# AD9102_DDS.net
KiCad netlist of a schematic drawn in Altium Designer
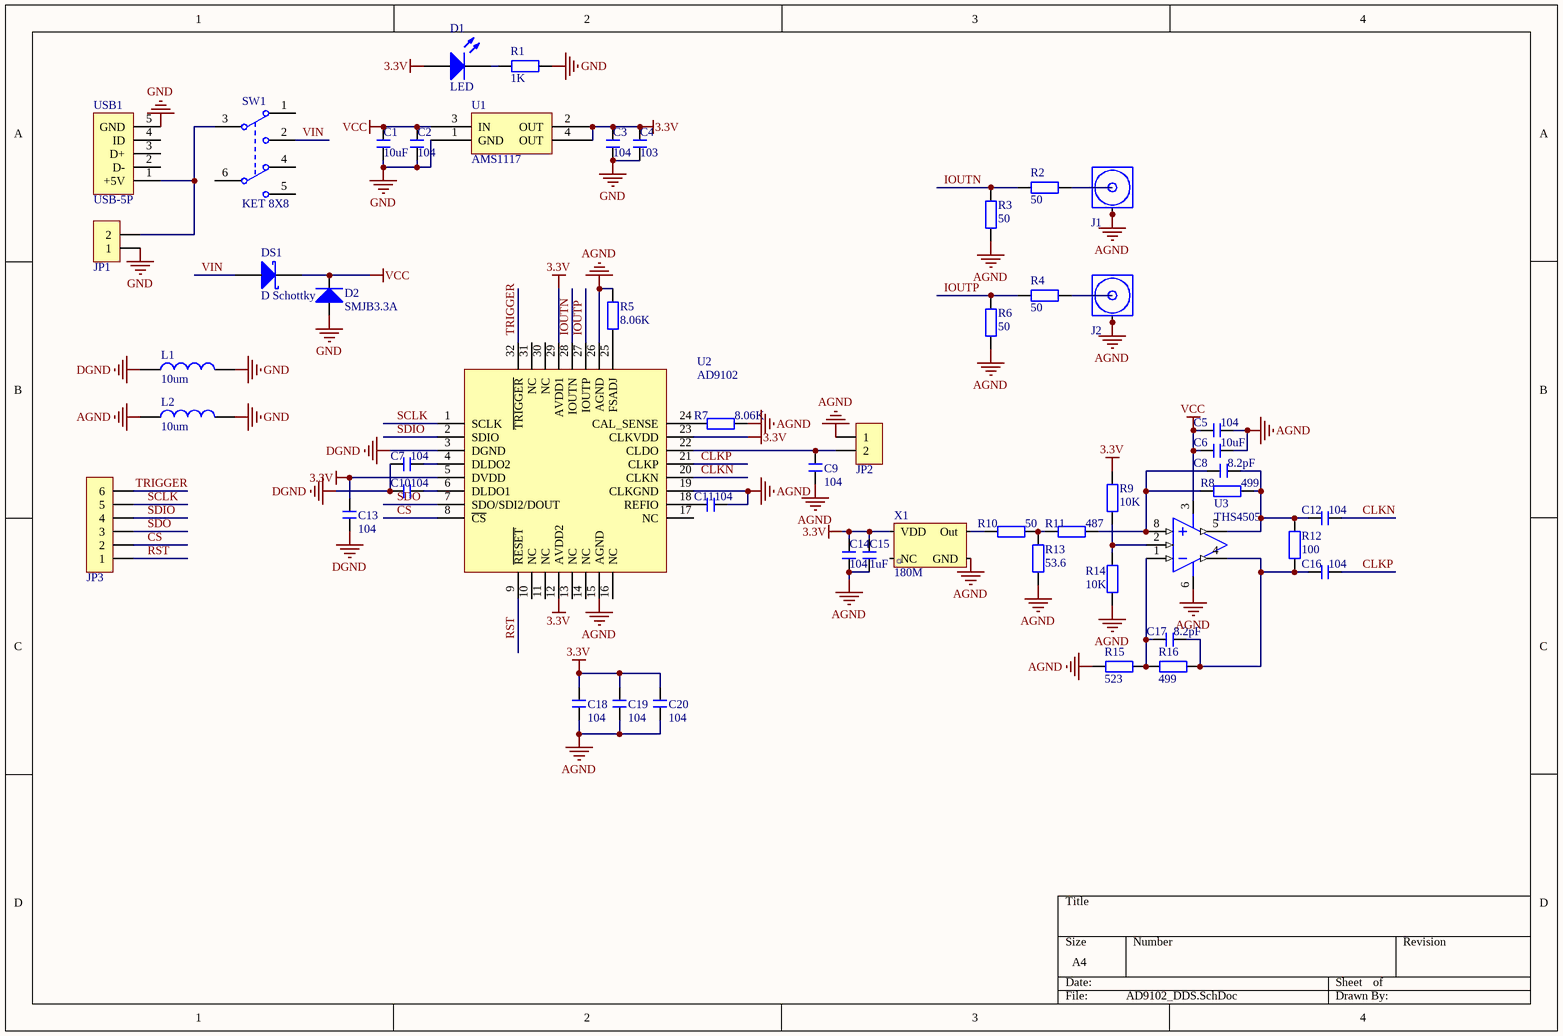
[diagram p0: AD9102_DDS.SchDoc]

(export (version "E")
  (design (tool "Eeschema 10.0.6"))
  (components
    (comp (ref "C1")
      (value "10uF")
      (footprint "C 0805")
      (description "无极性贴片电容")
      (fields (field (name "版权归属") "源创客"))
      (libsource (lib "电阻-电容-电感") (part "C"))
    )
    (comp (ref "C2")
      (value "104")
      (footprint "C 0603")
      (description "无极性贴片电容")
      (fields (field (name "版权归属") "源创客"))
      (libsource (lib "电阻-电容-电感") (part "C"))
    )
    (comp (ref "C3")
      (value "104")
      (footprint "C 0603")
      (description "无极性贴片电容")
      (fields (field (name "版权归属") "源创客"))
      (libsource (lib "电阻-电容-电感") (part "C"))
    )
    (comp (ref "C4")
      (value "103")
      (footprint "C 0603")
      (description "无极性贴片电容")
      (fields (field (name "版权归属") "源创客"))
      (libsource (lib "电阻-电容-电感") (part "C"))
    )
    (comp (ref "C5")
      (value "104")
      (footprint "C 0603")
      (description "无极性贴片电容")
      (fields (field (name "版权归属") "源创客"))
      (libsource (lib "电阻-电容-电感") (part "C"))
    )
    (comp (ref "C6")
      (value "10uF")
      (footprint "C 0603")
      (description "无极性贴片电容")
      (fields (field (name "版权归属") "源创客"))
      (libsource (lib "电阻-电容-电感") (part "C"))
    )
    (comp (ref "C7")
      (value "104")
      (footprint "C 0603")
      (description "无极性贴片电容")
      (fields (field (name "版权归属") "源创客"))
      (libsource (lib "电阻-电容-电感") (part "C"))
    )
    (comp (ref "C8")
      (value "8.2pF")
      (footprint "C 0603")
      (description "无极性贴片电容")
      (fields (field (name "版权归属") "源创客"))
      (libsource (lib "电阻-电容-电感") (part "C"))
    )
    (comp (ref "C9")
      (value "104")
      (footprint "C 0603")
      (description "无极性贴片电容")
      (fields (field (name "版权归属") "源创客"))
      (libsource (lib "电阻-电容-电感") (part "C"))
    )
    (comp (ref "C10")
      (value "104")
      (footprint "C 0603")
      (description "无极性贴片电容")
      (fields (field (name "版权归属") "源创客"))
      (libsource (lib "电阻-电容-电感") (part "C"))
    )
    (comp (ref "C11")
      (value "104")
      (footprint "C 0603")
      (description "无极性贴片电容")
      (fields (field (name "版权归属") "源创客"))
      (libsource (lib "电阻-电容-电感") (part "C"))
    )
    (comp (ref "C12")
      (value "104")
      (footprint "C 0603")
      (description "无极性贴片电容")
      (fields (field (name "版权归属") "源创客"))
      (libsource (lib "电阻-电容-电感") (part "C"))
    )
    (comp (ref "C13")
      (value "104")
      (footprint "C 0603")
      (description "无极性贴片电容")
      (fields (field (name "版权归属") "源创客"))
      (libsource (lib "电阻-电容-电感") (part "C"))
    )
    (comp (ref "C14")
      (value "104")
      (footprint "C 0603")
      (description "无极性贴片电容")
      (fields (field (name "版权归属") "源创客"))
      (libsource (lib "电阻-电容-电感") (part "C"))
    )
    (comp (ref "C15")
      (value "1uF")
      (footprint "C 0603")
      (description "无极性贴片电容")
      (fields (field (name "版权归属") "源创客"))
      (libsource (lib "电阻-电容-电感") (part "C"))
    )
    (comp (ref "C16")
      (value "104")
      (footprint "C 0603")
      (description "无极性贴片电容")
      (fields (field (name "版权归属") "源创客"))
      (libsource (lib "电阻-电容-电感") (part "C"))
    )
    (comp (ref "C17")
      (value "8.2pF")
      (footprint "C 0603")
      (description "无极性贴片电容")
      (fields (field (name "版权归属") "源创客"))
      (libsource (lib "电阻-电容-电感") (part "C"))
    )
    (comp (ref "C18")
      (value "104")
      (footprint "C 0603")
      (description "无极性贴片电容")
      (fields (field (name "版权归属") "源创客"))
      (libsource (lib "电阻-电容-电感") (part "C"))
    )
    (comp (ref "C19")
      (value "104")
      (footprint "C 0603")
      (description "无极性贴片电容")
      (fields (field (name "版权归属") "源创客"))
      (libsource (lib "电阻-电容-电感") (part "C"))
    )
    (comp (ref "C20")
      (value "104")
      (footprint "C 0603")
      (description "无极性贴片电容")
      (fields (field (name "版权归属") "源创客"))
      (libsource (lib "电阻-电容-电感") (part "C"))
    )
    (comp (ref "D1")
      (value "LED")
      (footprint "LED_0805")
      (description "发光二极管")
      (fields (field (name "PUBLISHER") "Altium Limited"))
      (libsource (lib "LIB") (part "LED"))
    )
    (comp (ref "D2")
      (value "TVS")
      (footprint "DIODE-SMA")
      (description "TVS保护")
      (fields (field (name "TYPE") "SMJB3.3A") (field (name "PUBLISHER") "Altium Limited"))
      (libsource (lib "LIB") (part "TVS"))
    )
    (comp (ref "DS1")
      (value "D Schottky")
      (footprint "DIODE-SMA")
      (description "Schottky Diode")
      (fields (field (name "PUBLISHER") "Altium Limited"))
      (libsource (lib "LIB") (part "D Schottky"))
    )
    (comp (ref "J1") (value "COAX") (footprint "MCX5.08-5-H") (libsource (lib "LIB") (part "COAX")))
    (comp (ref "J2") (value "COAX") (footprint "MCX5.08-5-H") (libsource (lib "LIB") (part "COAX")))
    (comp (ref "JP1")
      (value "HDR-1X2")
      (footprint "XH2.54-2P_H")
      (description "2P接插件")
      (fields (field (name "版权归属") "源创客"))
      (libsource (lib "") (part "Header 2_1"))
    )
    (comp (ref "JP2")
      (value "HDR-1X2")
      (footprint "HDR-1X2")
      (description "2P接插件")
      (fields (field (name "版权归属") "源创客"))
      (libsource (lib "接插件") (part "Header 2"))
    )
    (comp (ref "JP3")
      (value "HDR-1X6")
      (footprint "HDR-1X6")
      (description "6P接插件")
      (fields (field (name "版权归属") "源创客"))
      (libsource (lib "接插件") (part "Header 6"))
    )
    (comp (ref "L1")
      (value "10um")
      (footprint "L 0805")
      (description "小功率贴片电感")
      (fields (field (name "版权归属") "源创客"))
      (libsource (lib "电阻-电容-电感") (part "L"))
    )
    (comp (ref "L2")
      (value "10um")
      (footprint "L 0805")
      (description "小功率贴片电感")
      (fields (field (name "版权归属") "源创客"))
      (libsource (lib "电阻-电容-电感") (part "L"))
    )
    (comp (ref "R1")
      (value "1K")
      (footprint "R 0805")
      (description "贴片电阻")
      (fields (field (name "版权归属") "源创客"))
      (libsource (lib "电阻-电容-电感") (part "R"))
    )
    (comp (ref "R2")
      (value "50")
      (footprint "R 0603")
      (description "贴片电阻")
      (fields (field (name "版权归属") "源创客"))
      (libsource (lib "电阻-电容-电感") (part "R"))
    )
    (comp (ref "R3")
      (value "50")
      (footprint "R 0603")
      (description "贴片电阻")
      (fields (field (name "版权归属") "源创客"))
      (libsource (lib "电阻-电容-电感") (part "R"))
    )
    (comp (ref "R4")
      (value "50")
      (footprint "R 0603")
      (description "贴片电阻")
      (fields (field (name "版权归属") "源创客"))
      (libsource (lib "电阻-电容-电感") (part "R"))
    )
    (comp (ref "R5")
      (value "8.06K")
      (footprint "R 0603")
      (description "贴片电阻")
      (fields (field (name "版权归属") "源创客"))
      (libsource (lib "电阻-电容-电感") (part "R"))
    )
    (comp (ref "R6")
      (value "50")
      (footprint "R 0603")
      (description "贴片电阻")
      (fields (field (name "版权归属") "源创客"))
      (libsource (lib "电阻-电容-电感") (part "R"))
    )
    (comp (ref "R7")
      (value "8.06K")
      (footprint "R 0603")
      (description "贴片电阻")
      (fields (field (name "版权归属") "源创客"))
      (libsource (lib "电阻-电容-电感") (part "R"))
    )
    (comp (ref "R8")
      (value "499")
      (footprint "R 0603")
      (description "贴片电阻")
      (fields (field (name "版权归属") "源创客"))
      (libsource (lib "电阻-电容-电感") (part "R"))
    )
    (comp (ref "R9")
      (value "10K")
      (footprint "R 0603")
      (description "贴片电阻")
      (fields (field (name "版权归属") "源创客"))
      (libsource (lib "电阻-电容-电感") (part "R"))
    )
    (comp (ref "R10")
      (value "50")
      (footprint "R 0603")
      (description "贴片电阻")
      (fields (field (name "版权归属") "源创客"))
      (libsource (lib "电阻-电容-电感") (part "R"))
    )
    (comp (ref "R11")
      (value "487")
      (footprint "R 0603")
      (description "贴片电阻")
      (fields (field (name "版权归属") "源创客"))
      (libsource (lib "电阻-电容-电感") (part "R"))
    )
    (comp (ref "R12")
      (value "100")
      (footprint "R 0603")
      (description "贴片电阻")
      (fields (field (name "版权归属") "源创客"))
      (libsource (lib "电阻-电容-电感") (part "R"))
    )
    (comp (ref "R13")
      (value "53.6")
      (footprint "R 0603")
      (description "贴片电阻")
      (fields (field (name "版权归属") "源创客"))
      (libsource (lib "电阻-电容-电感") (part "R"))
    )
    (comp (ref "R14")
      (value "10K")
      (footprint "R 0603")
      (description "贴片电阻")
      (fields (field (name "版权归属") "源创客"))
      (libsource (lib "电阻-电容-电感") (part "R"))
    )
    (comp (ref "R15")
      (value "523")
      (footprint "R 0603")
      (description "贴片电阻")
      (fields (field (name "版权归属") "源创客"))
      (libsource (lib "电阻-电容-电感") (part "R"))
    )
    (comp (ref "R16")
      (value "499")
      (footprint "R 0603")
      (description "贴片电阻")
      (fields (field (name "版权归属") "源创客"))
      (libsource (lib "电阻-电容-电感") (part "R"))
    )
    (comp (ref "SW1")
      (value "KET 8X8")
      (footprint "KFT DIP-8X8")
      (description "8*8自锁开关")
      (fields (field (name "版权归属") "源创客"))
      (libsource (lib "按键-开关") (part "KET 8X8"))
    )
    (comp (ref "U1")
      (value "AMS1117")
      (footprint "SOT223_N")
      (description "线性稳压芯片")
      (libsource (lib "LIB") (part "ASM1117"))
    )
    (comp (ref "U2")
      (value "AD9102")
      (footprint "CP_32_12")
      (description "低功耗、14位、180MSPS数模转换器和波形发生器")
      (libsource (lib "LIB") (part "AD9102"))
    )
    (comp (ref "U3")
      (value "THS4505")
      (footprint "MSOP-MS8_M")
      (description "WIDEBAND, LOW-DISTORTION,FULLY DIFFERENTIAL AMPLIFIERS")
      (libsource (lib "LIB") (part "THS4505"))
    )
    (comp (ref "USB1")
      (value "USB-5P")
      (footprint "USB-MICRO_B")
      (description "微型USB母座")
      (fields (field (name "版权归属") "源创客"))
      (libsource (lib "接口类") (part "USB-5P"))
    )
    (comp (ref "X1")
      (value "XTAL")
      (footprint "X-CPX75")
      (description "有源晶振")
      (fields (field (name "FREQUENCY") "180M"))
      (libsource (lib "LIB") (part "XTAL_Oscillator"))
    )
  )
  (nets
    (net (code "1") (name "/CLKN") (class "Default")
      (node (ref "C12") (pin "1") (pinfunction "1_1") (pintype "passive"))
      (node (ref "U2") (pin "20") (pinfunction "CLKN_20") (pintype "passive"))
    )
    (net (code "2") (name "/CLKP") (class "Default")
      (node (ref "C16") (pin "1") (pinfunction "1_1") (pintype "passive"))
      (node (ref "U2") (pin "21") (pinfunction "CLKP_21") (pintype "passive"))
    )
    (net (code "3") (name "/IOUTN") (class "Default")
      (node (ref "R2") (pin "2") (pinfunction "2_2") (pintype "passive"))
      (node (ref "R3") (pin "2") (pinfunction "2_2") (pintype "passive"))
      (node (ref "U2") (pin "28") (pinfunction "IOUTN_28") (pintype "passive"))
    )
    (net (code "4") (name "/IOUTP") (class "Default")
      (node (ref "R4") (pin "2") (pinfunction "2_2") (pintype "passive"))
      (node (ref "R6") (pin "2") (pinfunction "2_2") (pintype "passive"))
      (node (ref "U2") (pin "27") (pinfunction "IOUTP_27") (pintype "passive"))
    )
    (net (code "5") (name "/RST") (class "Default")
      (node (ref "JP3") (pin "1") (pinfunction "1_1") (pintype "passive"))
      (node (ref "U2") (pin "9") (pinfunction "~{RESET}_9") (pintype "passive"))
    )
    (net (code "6") (name "/SCLK") (class "Default")
      (node (ref "JP3") (pin "5") (pinfunction "5_5") (pintype "passive"))
      (node (ref "U2") (pin "1") (pinfunction "SCLK_1") (pintype "passive"))
    )
    (net (code "7") (name "/SDIO") (class "Default")
      (node (ref "JP3") (pin "4") (pinfunction "4_4") (pintype "passive"))
      (node (ref "U2") (pin "2") (pinfunction "SDIO_2") (pintype "passive"))
    )
    (net (code "8") (name "/SDO") (class "Default")
      (node (ref "JP3") (pin "3") (pinfunction "3_3") (pintype "passive"))
      (node (ref "U2") (pin "7") (pinfunction "SDO/SDI2/DOUT_7") (pintype "passive"))
    )
    (net (code "9") (name "/TRIGGER") (class "Default")
      (node (ref "JP3") (pin "6") (pinfunction "6_6") (pintype "passive"))
      (node (ref "U2") (pin "32") (pinfunction "~{TRIGGER}_32") (pintype "passive"))
    )
    (net (code "10") (name "/VIN") (class "Default")
      (node (ref "DS1") (pin "1") (pinfunction "1_1") (pintype "passive"))
      (node (ref "SW1") (pin "2") (pinfunction "COM2_2") (pintype "passive"))
    )
    (net (code "11") (name "/~{CS}") (class "Default")
      (node (ref "JP3") (pin "2") (pinfunction "2_2") (pintype "passive"))
      (node (ref "U2") (pin "8") (pinfunction "~{CS}_8") (pintype "passive"))
    )
    (net (code "12") (name "3.3V") (class "Default")
      (node (ref "C13") (pin "2") (pinfunction "2_2") (pintype "passive"))
      (node (ref "C14") (pin "2") (pinfunction "2_2") (pintype "passive"))
      (node (ref "C15") (pin "2") (pinfunction "2_2") (pintype "passive"))
      (node (ref "C18") (pin "2") (pinfunction "2_2") (pintype "passive"))
      (node (ref "C19") (pin "2") (pinfunction "2_2") (pintype "passive"))
      (node (ref "C20") (pin "2") (pinfunction "2_2") (pintype "passive"))
      (node (ref "C3") (pin "2") (pinfunction "2_2") (pintype "passive"))
      (node (ref "C4") (pin "2") (pinfunction "2_2") (pintype "passive"))
      (node (ref "D1") (pin "1") (pinfunction "A_1") (pintype "passive"))
      (node (ref "R9") (pin "1") (pinfunction "1_1") (pintype "passive"))
      (node (ref "U1") (pin "2") (pinfunction "OUT_2") (pintype "passive"))
      (node (ref "U1") (pin "4") (pinfunction "OUT_4") (pintype "passive"))
      (node (ref "U2") (pin "12") (pinfunction "AVDD2_12") (pintype "passive"))
      (node (ref "U2") (pin "23") (pinfunction "CLKVDD_23") (pintype "passive"))
      (node (ref "U2") (pin "29") (pinfunction "AVDD1_29") (pintype "passive"))
      (node (ref "U2") (pin "5") (pinfunction "DVDD_5") (pintype "passive"))
      (node (ref "X1") (pin "4") (pinfunction "VDD_4") (pintype "passive"))
    )
    (net (code "13") (name "AGND") (class "Default")
      (node (ref "C11") (pin "1") (pinfunction "1_1") (pintype "passive"))
      (node (ref "C14") (pin "1") (pinfunction "1_1") (pintype "passive"))
      (node (ref "C15") (pin "1") (pinfunction "1_1") (pintype "passive"))
      (node (ref "C18") (pin "1") (pinfunction "1_1") (pintype "passive"))
      (node (ref "C19") (pin "1") (pinfunction "1_1") (pintype "passive"))
      (node (ref "C20") (pin "1") (pinfunction "1_1") (pintype "passive"))
      (node (ref "C5") (pin "1") (pinfunction "1_1") (pintype "passive"))
      (node (ref "C6") (pin "1") (pinfunction "1_1") (pintype "passive"))
      (node (ref "C9") (pin "1") (pinfunction "1_1") (pintype "passive"))
      (node (ref "J1") (pin "2") (pinfunction "GND_2") (pintype "passive"))
      (node (ref "J1") (pin "3") (pinfunction "GND_3") (pintype "passive"))
      (node (ref "J1") (pin "4") (pinfunction "GND_4") (pintype "passive"))
      (node (ref "J1") (pin "5") (pinfunction "GND_5") (pintype "passive"))
      (node (ref "J2") (pin "2") (pinfunction "GND_2") (pintype "passive"))
      (node (ref "J2") (pin "3") (pinfunction "GND_3") (pintype "passive"))
      (node (ref "J2") (pin "4") (pinfunction "GND_4") (pintype "passive"))
      (node (ref "J2") (pin "5") (pinfunction "GND_5") (pintype "passive"))
      (node (ref "JP2") (pin "1") (pinfunction "1_1") (pintype "passive"))
      (node (ref "L2") (pin "1") (pinfunction "1_1") (pintype "passive"))
      (node (ref "R13") (pin "2") (pinfunction "2_2") (pintype "passive"))
      (node (ref "R14") (pin "2") (pinfunction "2_2") (pintype "passive"))
      (node (ref "R15") (pin "2") (pinfunction "2_2") (pintype "passive"))
      (node (ref "R3") (pin "1") (pinfunction "1_1") (pintype "passive"))
      (node (ref "R5") (pin "2") (pinfunction "2_2") (pintype "passive"))
      (node (ref "R6") (pin "1") (pinfunction "1_1") (pintype "passive"))
      (node (ref "R7") (pin "2") (pinfunction "2_2") (pintype "passive"))
      (node (ref "U2") (pin "15") (pinfunction "AGND_15") (pintype "passive"))
      (node (ref "U2") (pin "19") (pinfunction "CLKGND_19") (pintype "passive"))
      (node (ref "U2") (pin "26") (pinfunction "AGND_26") (pintype "passive"))
      (node (ref "U3") (pin "6") (pinfunction "VS-_6") (pintype "power_in"))
      (node (ref "X1") (pin "2") (pinfunction "GND_2") (pintype "passive"))
    )
    (net (code "14") (name "DGND") (class "Default")
      (node (ref "C10") (pin "1") (pinfunction "1_1") (pintype "passive"))
      (node (ref "C13") (pin "1") (pinfunction "1_1") (pintype "passive"))
      (node (ref "C7") (pin "1") (pinfunction "1_1") (pintype "passive"))
      (node (ref "L1") (pin "1") (pinfunction "1_1") (pintype "passive"))
      (node (ref "U2") (pin "3") (pinfunction "DGND_3") (pintype "passive"))
    )
    (net (code "15") (name "GND") (class "Default")
      (node (ref "C1") (pin "1") (pinfunction "1_1") (pintype "passive"))
      (node (ref "C2") (pin "1") (pinfunction "1_1") (pintype "passive"))
      (node (ref "C3") (pin "1") (pinfunction "1_1") (pintype "passive"))
      (node (ref "C4") (pin "1") (pinfunction "1_1") (pintype "passive"))
      (node (ref "D2") (pin "1") (pinfunction "A_1") (pintype "passive"))
      (node (ref "JP1") (pin "1") (pinfunction "1_1") (pintype "passive"))
      (node (ref "L1") (pin "2") (pinfunction "2_2") (pintype "passive"))
      (node (ref "L2") (pin "2") (pinfunction "2_2") (pintype "passive"))
      (node (ref "R1") (pin "2") (pinfunction "2_2") (pintype "passive"))
      (node (ref "U1") (pin "1") (pinfunction "GND_1") (pintype "passive"))
      (node (ref "USB1") (pin "5") (pinfunction "GND_5") (pintype "passive"))
    )
    (net (code "16") (name "Net-(C8-Pad2)") (class "Default")
      (node (ref "C8") (pin "2") (pinfunction "2_2") (pintype "passive"))
      (node (ref "R11") (pin "1") (pinfunction "1_1") (pintype "passive"))
      (node (ref "R8") (pin "2") (pinfunction "2_2") (pintype "passive"))
      (node (ref "U3") (pin "8") (pinfunction "+IN_8") (pintype "input"))
    )
    (net (code "17") (name "Net-(D1-K)") (class "Default")
      (node (ref "D1") (pin "2") (pinfunction "K_2") (pintype "passive"))
      (node (ref "R1") (pin "1") (pinfunction "1_1") (pintype "passive"))
    )
    (net (code "18") (name "Net-(J1-Signal)") (class "Default")
      (node (ref "J1") (pin "1") (pinfunction "Signal_1") (pintype "passive"))
      (node (ref "R2") (pin "1") (pinfunction "1_1") (pintype "passive"))
    )
    (net (code "19") (name "Net-(J2-Signal)") (class "Default")
      (node (ref "J2") (pin "1") (pinfunction "Signal_1") (pintype "passive"))
      (node (ref "R4") (pin "1") (pinfunction "1_1") (pintype "passive"))
    )
    (net (code "20") (name "Net-(R10-Pad1)") (class "Default")
      (node (ref "R10") (pin "1") (pinfunction "1_1") (pintype "passive"))
      (node (ref "R11") (pin "2") (pinfunction "2_2") (pintype "passive"))
      (node (ref "R13") (pin "1") (pinfunction "1_1") (pintype "passive"))
    )
    (net (code "21") (name "Net-(R14-Pad1)") (class "Default")
      (node (ref "R14") (pin "1") (pinfunction "1_1") (pintype "passive"))
      (node (ref "R9") (pin "2") (pinfunction "2_2") (pintype "passive"))
      (node (ref "U3") (pin "2") (pinfunction "+IN_2") (pintype "input"))
    )
    (net (code "22") (name "Net-(SW1-NO1)") (class "Default")
      (node (ref "JP1") (pin "2") (pinfunction "2_2") (pintype "passive"))
      (node (ref "SW1") (pin "3") (pinfunction "NO1_3") (pintype "passive"))
      (node (ref "USB1") (pin "1") (pinfunction "+5V_1") (pintype "passive"))
    )
    (net (code "23") (name "Net-(U2-CAL_SENSE)") (class "Default")
      (node (ref "R7") (pin "1") (pinfunction "1_1") (pintype "passive"))
      (node (ref "U2") (pin "24") (pinfunction "CAL_SENSE_24") (pintype "passive"))
    )
    (net (code "24") (name "Net-(U2-CLDO)") (class "Default")
      (node (ref "C9") (pin "2") (pinfunction "2_2") (pintype "passive"))
      (node (ref "JP2") (pin "2") (pinfunction "2_2") (pintype "passive"))
      (node (ref "U2") (pin "22") (pinfunction "CLDO_22") (pintype "passive"))
    )
    (net (code "25") (name "Net-(U2-DLDO1)") (class "Default")
      (node (ref "C10") (pin "2") (pinfunction "2_2") (pintype "passive"))
      (node (ref "U2") (pin "6") (pinfunction "DLDO1_6") (pintype "passive"))
    )
    (net (code "26") (name "Net-(U2-DLDO2)") (class "Default")
      (node (ref "C7") (pin "2") (pinfunction "2_2") (pintype "passive"))
      (node (ref "U2") (pin "4") (pinfunction "DLDO2_4") (pintype "passive"))
    )
    (net (code "27") (name "Net-(U2-FSADJ)") (class "Default")
      (node (ref "R5") (pin "1") (pinfunction "1_1") (pintype "passive"))
      (node (ref "U2") (pin "25") (pinfunction "FSADJ_25") (pintype "passive"))
    )
    (net (code "28") (name "Net-(U2-REFIO)") (class "Default")
      (node (ref "C11") (pin "2") (pinfunction "2_2") (pintype "passive"))
      (node (ref "U2") (pin "18") (pinfunction "REFIO_18") (pintype "passive"))
    )
    (net (code "29") (name "Net-(U3--IN)") (class "Default")
      (node (ref "C17") (pin "2") (pinfunction "2_2") (pintype "passive"))
      (node (ref "R15") (pin "1") (pinfunction "1_1") (pintype "passive"))
      (node (ref "R16") (pin "2") (pinfunction "2_2") (pintype "passive"))
      (node (ref "U3") (pin "1") (pinfunction "-IN_1") (pintype "input"))
    )
    (net (code "30") (name "Net-(U3-VOUT+)") (class "Default")
      (node (ref "C16") (pin "2") (pinfunction "2_2") (pintype "passive"))
      (node (ref "C17") (pin "1") (pinfunction "1_1") (pintype "passive"))
      (node (ref "R12") (pin "2") (pinfunction "2_2") (pintype "passive"))
      (node (ref "R16") (pin "1") (pinfunction "1_1") (pintype "passive"))
      (node (ref "U3") (pin "4") (pinfunction "VOUT+_4") (pintype "output"))
    )
    (net (code "31") (name "Net-(U3-VOUT-)") (class "Default")
      (node (ref "C12") (pin "2") (pinfunction "2_2") (pintype "passive"))
      (node (ref "C8") (pin "1") (pinfunction "1_1") (pintype "passive"))
      (node (ref "R12") (pin "1") (pinfunction "1_1") (pintype "passive"))
      (node (ref "R8") (pin "1") (pinfunction "1_1") (pintype "passive"))
      (node (ref "U3") (pin "5") (pinfunction "VOUT-_5") (pintype "output"))
    )
    (net (code "32") (name "Net-(X1-Out)") (class "Default")
      (node (ref "R10") (pin "2") (pinfunction "2_2") (pintype "passive"))
      (node (ref "X1") (pin "3") (pinfunction "Out_3") (pintype "passive"))
    )
    (net (code "33") (name "VCC") (class "Default")
      (node (ref "C1") (pin "2") (pinfunction "2_2") (pintype "passive"))
      (node (ref "C2") (pin "2") (pinfunction "2_2") (pintype "passive"))
      (node (ref "C5") (pin "2") (pinfunction "2_2") (pintype "passive"))
      (node (ref "C6") (pin "2") (pinfunction "2_2") (pintype "passive"))
      (node (ref "D2") (pin "2") (pinfunction "K_2") (pintype "passive"))
      (node (ref "DS1") (pin "2") (pinfunction "2_2") (pintype "passive"))
      (node (ref "U1") (pin "3") (pinfunction "IN_3") (pintype "passive"))
      (node (ref "U3") (pin "3") (pinfunction "VS+_3") (pintype "power_in"))
    )
    (net (code "34") (name "unconnected-(SW1-COM2-Pad5)") (class "Default")
      (node (ref "SW1") (pin "5") (pinfunction "COM2_5") (pintype "passive"))
    )
    (net (code "35") (name "unconnected-(SW1-NC1-Pad1)") (class "Default")
      (node (ref "SW1") (pin "1") (pinfunction "NC1_1") (pintype "passive"))
    )
    (net (code "36") (name "unconnected-(SW1-NC2-Pad6)") (class "Default")
      (node (ref "SW1") (pin "6") (pinfunction "NC2_6") (pintype "passive"))
    )
    (net (code "37") (name "unconnected-(SW1-NO2-Pad4)") (class "Default")
      (node (ref "SW1") (pin "4") (pinfunction "NO2_4") (pintype "passive"))
    )
    (net (code "38") (name "unconnected-(U2-NC-Pad10)") (class "Default")
      (node (ref "U2") (pin "10") (pinfunction "NC_10") (pintype "passive"))
    )
    (net (code "39") (name "unconnected-(U2-NC-Pad11)") (class "Default")
      (node (ref "U2") (pin "11") (pinfunction "NC_11") (pintype "passive"))
    )
    (net (code "40") (name "unconnected-(U2-NC-Pad13)") (class "Default")
      (node (ref "U2") (pin "13") (pinfunction "NC_13") (pintype "passive"))
    )
    (net (code "41") (name "unconnected-(U2-NC-Pad14)") (class "Default")
      (node (ref "U2") (pin "14") (pinfunction "NC_14") (pintype "passive"))
    )
    (net (code "42") (name "unconnected-(U2-NC-Pad16)") (class "Default")
      (node (ref "U2") (pin "16") (pinfunction "NC_16") (pintype "passive"))
    )
    (net (code "43") (name "unconnected-(U2-NC-Pad17)") (class "Default")
      (node (ref "U2") (pin "17") (pinfunction "NC_17") (pintype "passive"))
    )
    (net (code "44") (name "unconnected-(U2-NC-Pad30)") (class "Default")
      (node (ref "U2") (pin "30") (pinfunction "NC_30") (pintype "passive"))
    )
    (net (code "45") (name "unconnected-(U2-NC-Pad31)") (class "Default")
      (node (ref "U2") (pin "31") (pinfunction "NC_31") (pintype "passive"))
    )
    (net (code "46") (name "unconnected-(USB1-D+-Pad3)") (class "Default")
      (node (ref "USB1") (pin "3") (pinfunction "D+_3") (pintype "passive"))
    )
    (net (code "47") (name "unconnected-(USB1-D--Pad2)") (class "Default")
      (node (ref "USB1") (pin "2") (pinfunction "D-_2") (pintype "passive"))
    )
    (net (code "48") (name "unconnected-(USB1-ID-Pad4)") (class "Default")
      (node (ref "USB1") (pin "4") (pinfunction "ID_4") (pintype "passive"))
    )
    (net (code "49") (name "unconnected-(X1-NC-Pad1)") (class "Default")
      (node (ref "X1") (pin "1") (pinfunction "NC_1") (pintype "passive"))
    )
  )
)
